# BotInd.net
KiCad netlist of a schematic drawn in Altium Designer
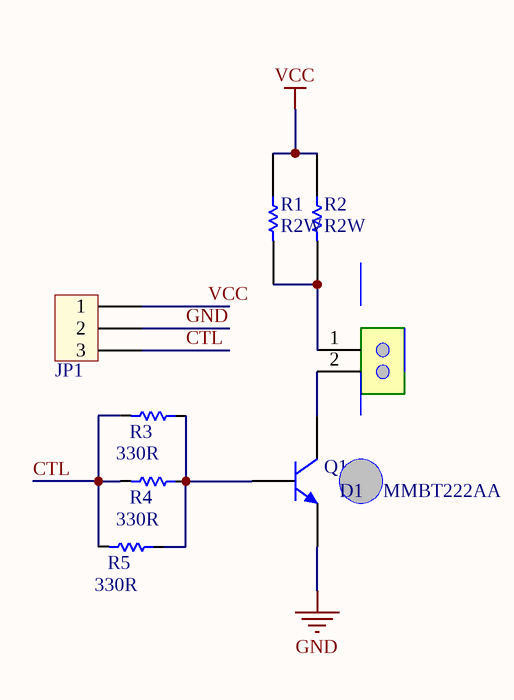
[diagram p0: BotInd.SchDoc]

(export (version "E")
  (design (tool "Eeschema 10.0.6"))
  (components
    (comp (ref "D1")
      (value "DOMINO")
      (footprint "Domino2_350")
      (libsource (lib "Thach") (part "Domino2_small"))
    )
    (comp (ref "JP1")
      (value "HEAD3")
      (footprint "HEAD3")
      (description "Connector 3")
      (libsource (lib "Thach") (part "HEAD3"))
    )
    (comp (ref "Q1")
      (value "MMBT222AA")
      (footprint "SOT23-3")
      (description "NPN General Purpose Amplifier")
      (fields (field (name "PUBLISHER") "Altium Limited"))
      (libsource (lib "Thach") (part "MMBT222AA"))
    )
    (comp (ref "R1") (value "R2W") (footprint "R 2W") (libsource (lib "Thach") (part "R2W")))
    (comp (ref "R2") (value "R2W") (footprint "R 2W") (libsource (lib "Thach") (part "R2W")))
    (comp (ref "R3")
      (value "0805_R")
      (footprint "0805_R")
      (description "0805 SMD resistor")
      (fields (field (name "ALTIUM_UNNAMED_1") "330R"))
      (libsource (lib "Thach") (part "0805_R"))
    )
    (comp (ref "R4")
      (value "0805_R")
      (footprint "0805_R")
      (description "0805 SMD resistor")
      (fields (field (name "ALTIUM_UNNAMED_1") "330R"))
      (libsource (lib "Thach") (part "0805_R"))
    )
    (comp (ref "R5")
      (value "0805_R")
      (footprint "0805_R")
      (description "0805 SMD resistor")
      (fields (field (name "ALTIUM_UNNAMED_1") "330R"))
      (libsource (lib "Thach") (part "0805_R"))
    )
  )
  (nets
    (net (code "1") (name "/CTL") (class "Default")
      (node (ref "JP1") (pin "3") (pinfunction "3_3") (pintype "passive"))
      (node (ref "R3") (pin "2") (pinfunction "2_2") (pintype "passive"))
      (node (ref "R4") (pin "2") (pinfunction "2_2") (pintype "passive"))
      (node (ref "R5") (pin "2") (pinfunction "2_2") (pintype "passive"))
    )
    (net (code "2") (name "GND") (class "Default")
      (node (ref "JP1") (pin "2") (pinfunction "2_2") (pintype "passive"))
      (node (ref "Q1") (pin "2") (pinfunction "E_2") (pintype "passive"))
    )
    (net (code "3") (name "Net-(D1-Pad1)") (class "Default")
      (node (ref "D1") (pin "1") (pintype "passive"))
      (node (ref "R1") (pin "2") (pinfunction "2_2") (pintype "passive"))
      (node (ref "R2") (pin "2") (pinfunction "2_2") (pintype "passive"))
    )
    (net (code "4") (name "Net-(Q1-B)") (class "Default")
      (node (ref "Q1") (pin "1") (pinfunction "B_1") (pintype "passive"))
      (node (ref "R3") (pin "1") (pinfunction "1_1") (pintype "passive"))
      (node (ref "R4") (pin "1") (pinfunction "1_1") (pintype "passive"))
      (node (ref "R5") (pin "1") (pinfunction "1_1") (pintype "passive"))
    )
    (net (code "5") (name "Net-(Q1-C)") (class "Default")
      (node (ref "D1") (pin "2") (pintype "passive"))
      (node (ref "Q1") (pin "3") (pinfunction "C_3") (pintype "passive"))
    )
    (net (code "6") (name "VCC") (class "Default")
      (node (ref "JP1") (pin "1") (pinfunction "1_1") (pintype "passive"))
      (node (ref "R1") (pin "1") (pinfunction "1_1") (pintype "passive"))
      (node (ref "R2") (pin "1") (pinfunction "1_1") (pintype "passive"))
    )
  )
)
